# openSX70_ALADDIN_V381_20180125.net
KiCad netlist of a schematic drawn in EAGLE
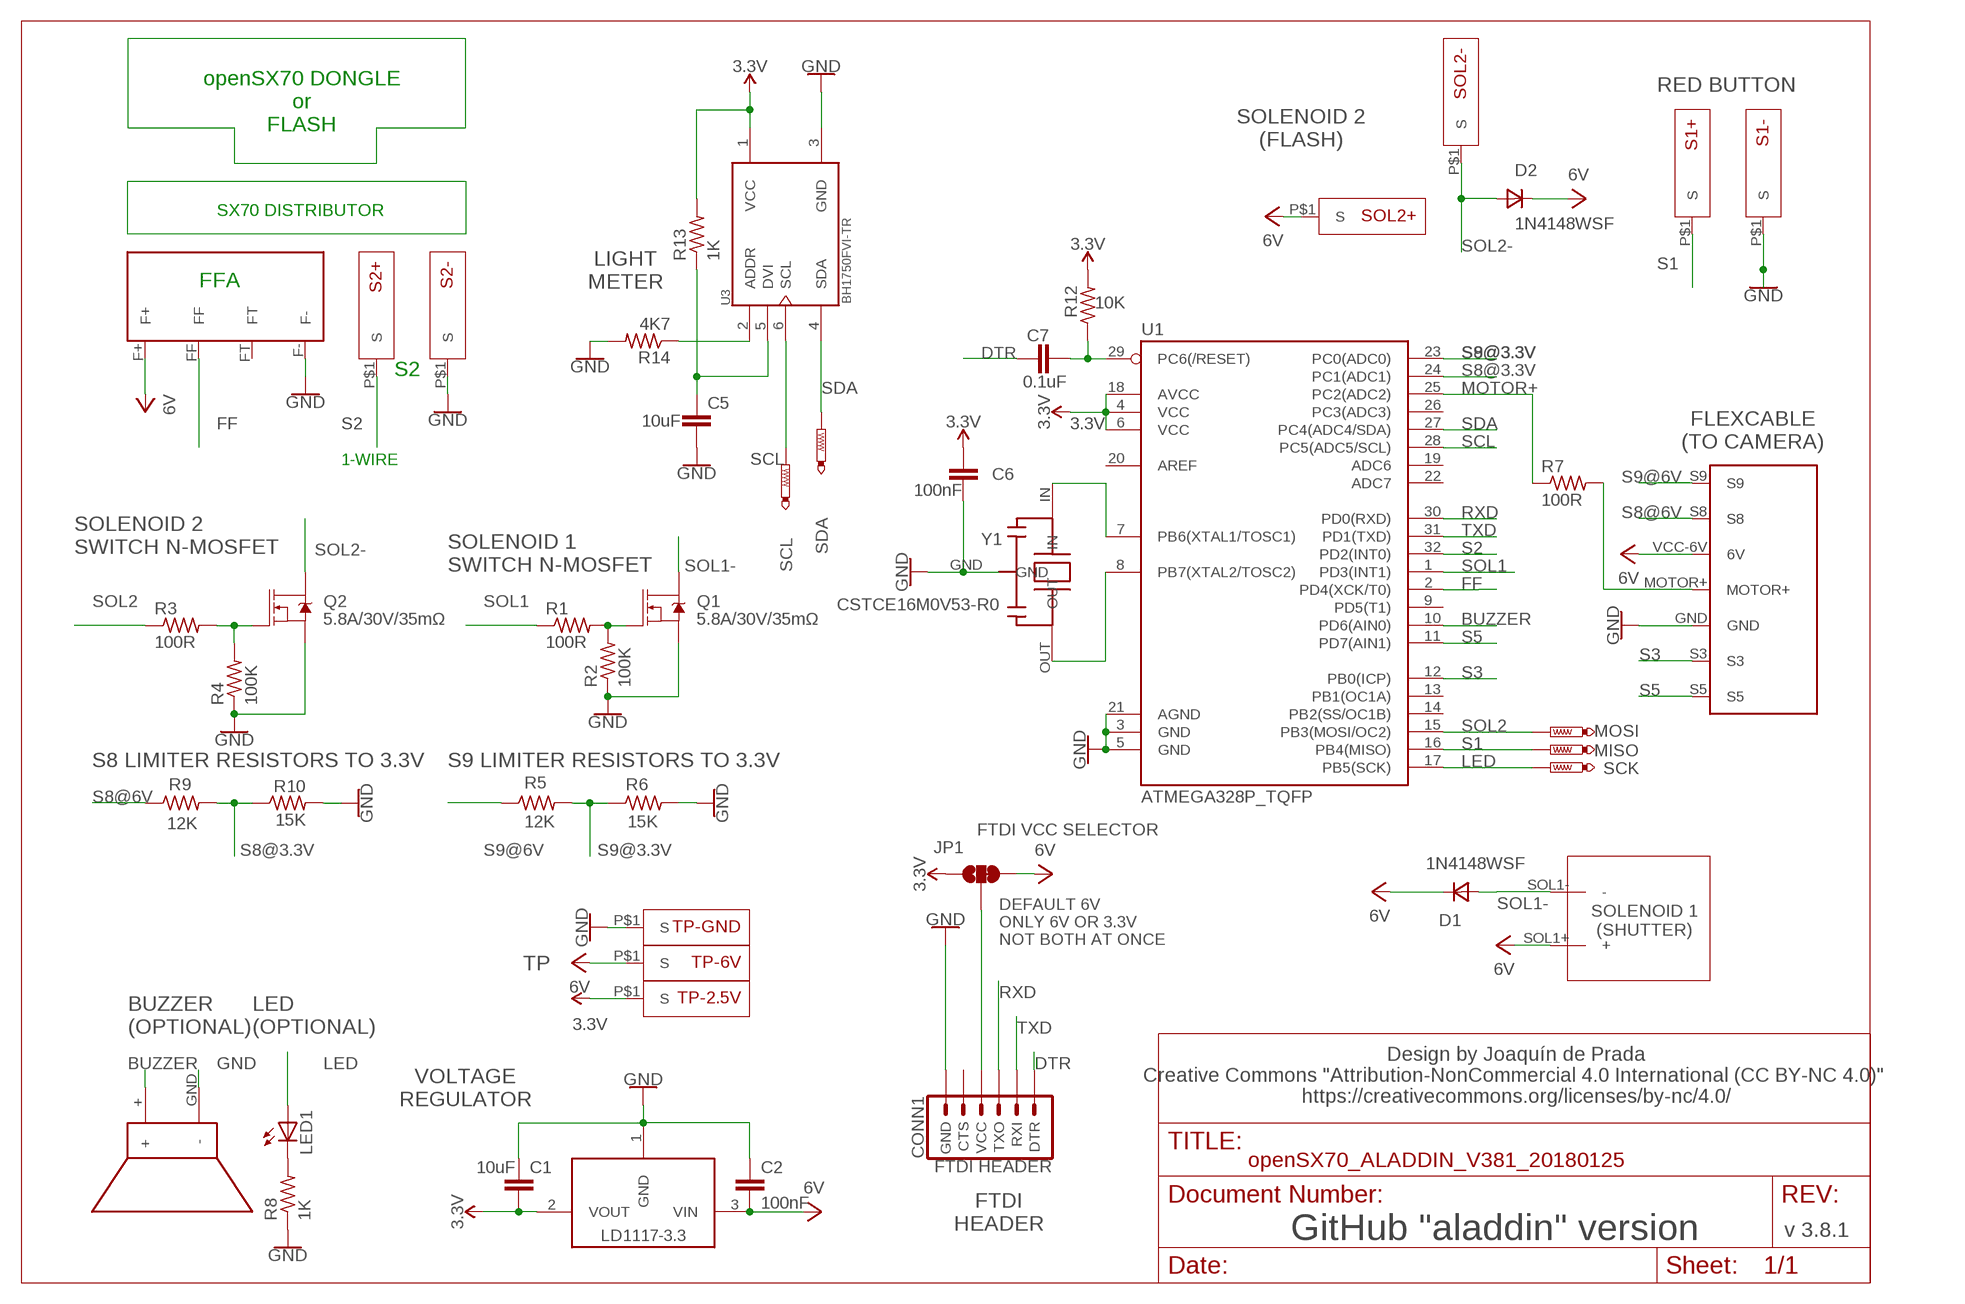
[diagram p0: schematic, sheet 1]

(export (version "E")
  (design (tool "Eeschema 10.0.6"))
  (components
    (comp (ref "BUZZ1")
      (value "CSET8-5G")
      (footprint "eagle-import:CSET8-5G_PACKAGE")
      (libsource (lib "eagle-import") (part "CSET8-5G"))
    )
    (comp (ref "C1")
      (value "10uF")
      (footprint "eagle-import:0603")
      (libsource (lib "eagle-import") (part "10UF-0603-6.3V-20%"))
    )
    (comp (ref "C2")
      (value "100nF")
      (footprint "eagle-import:C0603K")
      (libsource (lib "eagle-import") (part "C-EUC0603K"))
    )
    (comp (ref "C5")
      (value "10uF")
      (footprint "eagle-import:0603")
      (libsource (lib "eagle-import") (part "10UF-0603-6.3V-20%"))
    )
    (comp (ref "C6")
      (value "100nF")
      (footprint "eagle-import:C0603")
      (libsource (lib "eagle-import") (part "C-EUC0603"))
    )
    (comp (ref "C7")
      (value "0.1uF")
      (footprint "eagle-import:0603")
      (libsource (lib "eagle-import") (part "0.1UF-0603-25V-(+80/-20%)"))
    )
    (comp (ref "CONN1")
      (value "FTDI HEADER")
      (footprint "eagle-import:1X06")
      (libsource (lib "eagle-import") (part "6_PIN_SERIAL_TARGET"))
    )
    (comp (ref "D1")
      (value "1N4148WSF")
      (footprint "eagle-import:SOD323")
      (fields (field (name "MPN") "CDSOD323-T05C"))
      (libsource (lib "eagle-import") (part "DSOD323"))
    )
    (comp (ref "D2")
      (value "1N4148WSF")
      (footprint "eagle-import:SOD323")
      (fields (field (name "MPN") "CDSOD323-T05C"))
      (libsource (lib "eagle-import") (part "DSOD323"))
    )
    (comp (ref "JP1")
      (value "FTDI VCC SELECTOR")
      (footprint "eagle-import:SMT-JUMPER_3_1-NC_TRACE_SILK")
      (libsource (lib "eagle-import") (part "JUMPER-SMT_3_1-NC_TRACE_SILK"))
    )
    (comp (ref "LD11172.5V")
      (value "LD1117 3.3V")
      (footprint "eagle-import:SOT223")
      (fields (field (name "MF") "Advanced Monolithic Systems") (field (name "MP") "AMS1117-5.0"))
      (libsource (lib "eagle-import") (part "LD1117-3.3"))
    )
    (comp (ref "LED1")
      (value "LEDCHIPLED_0805")
      (footprint "eagle-import:CHIPLED_0805")
      (libsource (lib "eagle-import") (part "LEDCHIPLED_0805"))
    )
    (comp (ref "MISO")
      (value "PTR1TP08R")
      (footprint "eagle-import:TP08R")
      (libsource (lib "eagle-import") (part "PTR1TP08R"))
    )
    (comp (ref "MOSI")
      (value "PTR1TP08R")
      (footprint "eagle-import:TP08R")
      (libsource (lib "eagle-import") (part "PTR1TP08R"))
    )
    (comp (ref "Q1")
      (value "5.8A/30V/35mΩ")
      (footprint "eagle-import:SOT23-3")
      (libsource (lib "eagle-import") (part "MOSFET-NCH-AO3404A"))
    )
    (comp (ref "Q2")
      (value "5.8A/30V/35mΩ")
      (footprint "eagle-import:SOT23-3")
      (libsource (lib "eagle-import") (part "MOSFET-NCH-AO3404A"))
    )
    (comp (ref "R1")
      (value "100R")
      (footprint "eagle-import:R0603")
      (libsource (lib "eagle-import") (part "R-US_R0603"))
    )
    (comp (ref "R2")
      (value "100K")
      (footprint "eagle-import:R0603")
      (libsource (lib "eagle-import") (part "R-US_R0603"))
    )
    (comp (ref "R3")
      (value "100R")
      (footprint "eagle-import:R0603")
      (libsource (lib "eagle-import") (part "R-US_R0603"))
    )
    (comp (ref "R4")
      (value "100K")
      (footprint "eagle-import:R0603")
      (libsource (lib "eagle-import") (part "R-US_R0603"))
    )
    (comp (ref "R5")
      (value "12K")
      (footprint "eagle-import:R0603")
      (libsource (lib "eagle-import") (part "R-US_R0603"))
    )
    (comp (ref "R6")
      (value "15K")
      (footprint "eagle-import:R0603")
      (libsource (lib "eagle-import") (part "R-US_R0603"))
    )
    (comp (ref "R7")
      (value "100R")
      (footprint "eagle-import:R0603")
      (libsource (lib "eagle-import") (part "R-US_R0603"))
    )
    (comp (ref "R8")
      (value "1K")
      (footprint "eagle-import:R0603")
      (libsource (lib "eagle-import") (part "R-US_R0603"))
    )
    (comp (ref "R9")
      (value "12K")
      (footprint "eagle-import:R0603")
      (libsource (lib "eagle-import") (part "R-US_R0603"))
    )
    (comp (ref "R10")
      (value "15K")
      (footprint "eagle-import:R0603")
      (libsource (lib "eagle-import") (part "R-US_R0603"))
    )
    (comp (ref "R12")
      (value "10K")
      (footprint "eagle-import:R0603")
      (libsource (lib "eagle-import") (part "R-US_R0603"))
    )
    (comp (ref "R13")
      (value "1K")
      (footprint "eagle-import:R0603")
      (libsource (lib "eagle-import") (part "R-US_R0603"))
    )
    (comp (ref "R14")
      (value "4K7")
      (footprint "eagle-import:R0603")
      (libsource (lib "eagle-import") (part "R-US_R0603"))
    )
    (comp (ref "S1+")
      (value "SX70-S-PAD-NEW")
      (footprint "eagle-import:SX70-S-PAD2")
      (libsource (lib "eagle-import") (part "SX70-S-PAD-NEW"))
    )
    (comp (ref "S1-")
      (value "SX70-S-PAD-NEW")
      (footprint "eagle-import:SX70-S-PAD2")
      (libsource (lib "eagle-import") (part "SX70-S-PAD-NEW"))
    )
    (comp (ref "S2+")
      (value "SX70-S-PAD-NEW")
      (footprint "eagle-import:SX70-S-PAD2")
      (libsource (lib "eagle-import") (part "SX70-S-PAD-NEW"))
    )
    (comp (ref "S2-")
      (value "SX70-S-PAD-NEW")
      (footprint "eagle-import:SX70-S-PAD2")
      (libsource (lib "eagle-import") (part "SX70-S-PAD-NEW"))
    )
    (comp (ref "SCK")
      (value "PTR1TP08R")
      (footprint "eagle-import:TP08R")
      (libsource (lib "eagle-import") (part "PTR1TP08R"))
    )
    (comp (ref "SCL")
      (value "PTR1TP08R")
      (footprint "eagle-import:TP08R")
      (libsource (lib "eagle-import") (part "PTR1TP08R"))
    )
    (comp (ref "SDA")
      (value "PTR1TP08R")
      (footprint "eagle-import:TP08R")
      (libsource (lib "eagle-import") (part "PTR1TP08R"))
    )
    (comp (ref "SOL1")
      (value "SX70-SOLENOID1-2PADS")
      (footprint "eagle-import:SX70-SOLENOID1-2")
      (libsource (lib "eagle-import") (part "SX70-SOLENOID1-2PADS"))
    )
    (comp (ref "SOL2+")
      (value "SX70-S-PAD-NEW")
      (footprint "eagle-import:SX70-S-PAD2")
      (libsource (lib "eagle-import") (part "SX70-S-PAD-NEW"))
    )
    (comp (ref "SOL2-")
      (value "SX70-S-PAD-NEW")
      (footprint "eagle-import:SX70-S-PAD2")
      (libsource (lib "eagle-import") (part "SX70-S-PAD-NEW"))
    )
    (comp (ref "TP-2.5V")
      (value "SX70-S-PAD-NEW")
      (footprint "eagle-import:SX70-S-PAD2")
      (libsource (lib "eagle-import") (part "SX70-S-PAD-NEW"))
    )
    (comp (ref "TP-6V")
      (value "SX70-S-PAD-NEW")
      (footprint "eagle-import:SX70-S-PAD2")
      (libsource (lib "eagle-import") (part "SX70-S-PAD-NEW"))
    )
    (comp (ref "TP-GND")
      (value "SX70-S-PAD-NEW")
      (footprint "eagle-import:SX70-S-PAD2")
      (libsource (lib "eagle-import") (part "SX70-S-PAD-NEW"))
    )
    (comp (ref "U$1")
      (value "SX70-7-PAD")
      (footprint "eagle-import:SX70-7-PAD")
      (libsource (lib "eagle-import") (part "SX70-7-PAD"))
    )
    (comp (ref "U$2")
      (value "FFA")
      (footprint "eagle-import:FFA-PAD-PACKAGE")
      (libsource (lib "eagle-import") (part "SX70-FFA-PAD"))
    )
    (comp (ref "U1")
      (value "ATMEGA328P_TQFP")
      (footprint "eagle-import:TQFP32-08")
      (libsource (lib "eagle-import") (part "ATMEGA328P_TQFP"))
    )
    (comp (ref "U3")
      (value "BH1750FVI-TR")
      (footprint "eagle-import:SOTFL50P300X75-6N")
      (fields (field (name "MF") "Rohm"))
      (libsource (lib "eagle-import") (part "BH1750FVI-TR"))
    )
    (comp (ref "Y1")
      (value "CSTCE16M0V53-R0")
      (footprint "eagle-import:CFP95P160X100-3N")
      (fields (field (name "MF") "Murata"))
      (libsource (lib "eagle-import") (part "CSTCE16M0V53-R0"))
    )
  )
  (nets
    (net (code "1") (name "/BUZZER") (class "Default")
      (node (ref "BUZZ1") (pin "+") (pinfunction "+_+") (pintype "bidirectional"))
      (node (ref "U1") (pin "10") (pinfunction "PD6(AIN0)_10") (pintype "bidirectional"))
    )
    (net (code "2") (name "/DTR") (class "Default")
      (node (ref "C7") (pin "1") (pinfunction "1_1") (pintype "passive"))
      (node (ref "CONN1") (pin "1") (pinfunction "DTR_1") (pintype "passive"))
    )
    (net (code "3") (name "/FF") (class "Default")
      (node (ref "U$2") (pin "FF") (pinfunction "FF_FF") (pintype "bidirectional"))
      (node (ref "U1") (pin "2") (pinfunction "PD4(XCK/T0)_2") (pintype "bidirectional"))
    )
    (net (code "4") (name "/LED") (class "Default")
      (node (ref "LED1") (pin "A") (pinfunction "A_A") (pintype "passive"))
      (node (ref "SCK") (pin "TP") (pinfunction "TP_TP") (pintype "input"))
      (node (ref "U1") (pin "17") (pinfunction "PB5(SCK)_17") (pintype "bidirectional"))
    )
    (net (code "5") (name "/MOTOR+") (class "Default")
      (node (ref "R7") (pin "1") (pinfunction "1_1") (pintype "passive"))
      (node (ref "U1") (pin "25") (pinfunction "PC2(ADC2)_25") (pintype "bidirectional"))
    )
    (net (code "6") (name "/RXD") (class "Default")
      (node (ref "CONN1") (pin "3") (pinfunction "TXO_3") (pintype "passive"))
      (node (ref "U1") (pin "30") (pinfunction "PD0(RXD)_30") (pintype "bidirectional"))
    )
    (net (code "7") (name "/S1") (class "Default")
      (node (ref "MISO") (pin "TP") (pinfunction "TP_TP") (pintype "input"))
      (node (ref "S1+") (pin "P$1") (pinfunction "S_P$1") (pintype "bidirectional"))
      (node (ref "U1") (pin "16") (pinfunction "PB4(MISO)_16") (pintype "bidirectional"))
    )
    (net (code "8") (name "/S2") (class "Default")
      (node (ref "S2+") (pin "P$1") (pinfunction "S_P$1") (pintype "bidirectional"))
      (node (ref "U1") (pin "32") (pinfunction "PD2(INT0)_32") (pintype "bidirectional"))
    )
    (net (code "9") (name "/S3") (class "Default")
      (node (ref "U$1") (pin "S3") (pinfunction "S3_S3") (pintype "bidirectional"))
      (node (ref "U1") (pin "12") (pinfunction "PB0(ICP)_12") (pintype "bidirectional"))
    )
    (net (code "10") (name "/S5") (class "Default")
      (node (ref "U$1") (pin "S5") (pinfunction "S5_S5") (pintype "bidirectional"))
      (node (ref "U1") (pin "11") (pinfunction "PD7(AIN1)_11") (pintype "bidirectional"))
    )
    (net (code "11") (name "/S8@3.3V") (class "Default")
      (node (ref "R10") (pin "1") (pinfunction "1_1") (pintype "passive"))
      (node (ref "R9") (pin "2") (pinfunction "2_2") (pintype "passive"))
      (node (ref "U1") (pin "24") (pinfunction "PC1(ADC1)_24") (pintype "bidirectional"))
    )
    (net (code "12") (name "/S8@6V") (class "Default")
      (node (ref "R9") (pin "1") (pinfunction "1_1") (pintype "passive"))
      (node (ref "U$1") (pin "S8") (pinfunction "S8_S8") (pintype "bidirectional"))
    )
    (net (code "13") (name "/S9@3.3V") (class "Default")
      (node (ref "R5") (pin "2") (pinfunction "2_2") (pintype "passive"))
      (node (ref "R6") (pin "1") (pinfunction "1_1") (pintype "passive"))
      (node (ref "U1") (pin "23") (pinfunction "PC0(ADC0)_23") (pintype "bidirectional"))
    )
    (net (code "14") (name "/S9@6V") (class "Default")
      (node (ref "R5") (pin "1") (pinfunction "1_1") (pintype "passive"))
      (node (ref "U$1") (pin "S9") (pinfunction "S9_S9") (pintype "bidirectional"))
    )
    (net (code "15") (name "/SCL") (class "Default")
      (node (ref "SCL") (pin "TP") (pinfunction "TP_TP") (pintype "input"))
      (node (ref "U1") (pin "28") (pinfunction "PC5(ADC5/SCL)_28") (pintype "bidirectional"))
      (node (ref "U3") (pin "6") (pinfunction "SCL_6") (pintype "input"))
    )
    (net (code "16") (name "/SDA") (class "Default")
      (node (ref "SDA") (pin "TP") (pinfunction "TP_TP") (pintype "input"))
      (node (ref "U1") (pin "27") (pinfunction "PC4(ADC4/SDA)_27") (pintype "bidirectional"))
      (node (ref "U3") (pin "4") (pinfunction "SDA_4") (pintype "bidirectional"))
    )
    (net (code "17") (name "/SOL1") (class "Default")
      (node (ref "R1") (pin "1") (pinfunction "1_1") (pintype "passive"))
      (node (ref "U1") (pin "1") (pinfunction "PD3(INT1)_1") (pintype "bidirectional"))
    )
    (net (code "18") (name "/SOL1-") (class "Default")
      (node (ref "D1") (pin "2") (pinfunction "A_2") (pintype "passive"))
      (node (ref "Q1") (pin "3") (pinfunction "D_3") (pintype "bidirectional"))
      (node (ref "SOL1") (pin "SOL1-") (pinfunction "-_SOL1-") (pintype "bidirectional"))
    )
    (net (code "19") (name "/SOL2") (class "Default")
      (node (ref "MOSI") (pin "TP") (pinfunction "TP_TP") (pintype "input"))
      (node (ref "R3") (pin "1") (pinfunction "1_1") (pintype "passive"))
      (node (ref "U1") (pin "15") (pinfunction "PB3(MOSI/OC2)_15") (pintype "bidirectional"))
    )
    (net (code "20") (name "/SOL2-") (class "Default")
      (node (ref "D2") (pin "2") (pinfunction "A_2") (pintype "passive"))
      (node (ref "Q2") (pin "3") (pinfunction "D_3") (pintype "bidirectional"))
      (node (ref "SOL2-") (pin "P$1") (pinfunction "S_P$1") (pintype "bidirectional"))
    )
    (net (code "21") (name "/TXD") (class "Default")
      (node (ref "CONN1") (pin "2") (pinfunction "RXI_2") (pintype "passive"))
      (node (ref "U1") (pin "31") (pinfunction "PD1(TXD)_31") (pintype "bidirectional"))
    )
    (net (code "22") (name "3.3V") (class "Default")
      (node (ref "C1") (pin "2") (pinfunction "2_2") (pintype "passive"))
      (node (ref "C6") (pin "1") (pinfunction "1_1") (pintype "passive"))
      (node (ref "JP1") (pin "1") (pinfunction "1_1") (pintype "passive"))
      (node (ref "LD11172.5V") (pin "2") (pinfunction "VOUT_2") (pintype "bidirectional"))
      (node (ref "R12") (pin "2") (pinfunction "2_2") (pintype "passive"))
      (node (ref "R13") (pin "2") (pinfunction "2_2") (pintype "passive"))
      (node (ref "TP-2.5V") (pin "P$1") (pinfunction "S_P$1") (pintype "bidirectional"))
      (node (ref "U1") (pin "18") (pinfunction "AVCC_18") (pintype "bidirectional"))
      (node (ref "U1") (pin "4") (pinfunction "VCC_4") (pintype "bidirectional"))
      (node (ref "U1") (pin "6") (pinfunction "VCC_6") (pintype "bidirectional"))
      (node (ref "U3") (pin "1") (pinfunction "VCC_1") (pintype "power_in"))
    )
    (net (code "23") (name "6V") (class "Default")
      (node (ref "C2") (pin "2") (pinfunction "2_2") (pintype "passive"))
      (node (ref "D1") (pin "1") (pinfunction "C_1") (pintype "passive"))
      (node (ref "D2") (pin "1") (pinfunction "C_1") (pintype "passive"))
      (node (ref "JP1") (pin "3") (pinfunction "3_3") (pintype "passive"))
      (node (ref "LD11172.5V") (pin "3") (pinfunction "VIN_3") (pintype "bidirectional"))
      (node (ref "SOL1") (pin "SOL1+") (pinfunction "+_SOL1+") (pintype "bidirectional"))
      (node (ref "SOL2+") (pin "P$1") (pinfunction "S_P$1") (pintype "bidirectional"))
      (node (ref "TP-6V") (pin "P$1") (pinfunction "S_P$1") (pintype "bidirectional"))
      (node (ref "U$1") (pin "VCC-6V") (pinfunction "6V_VCC-6V") (pintype "bidirectional"))
      (node (ref "U$2") (pin "F+") (pinfunction "F+_F+") (pintype "bidirectional"))
    )
    (net (code "24") (name "GND") (class "Default")
      (node (ref "BUZZ1") (pin "GND") (pinfunction "-_GND") (pintype "bidirectional"))
      (node (ref "C1") (pin "1") (pinfunction "1_1") (pintype "passive"))
      (node (ref "C2") (pin "1") (pinfunction "1_1") (pintype "passive"))
      (node (ref "C5") (pin "2") (pinfunction "2_2") (pintype "passive"))
      (node (ref "C6") (pin "2") (pinfunction "2_2") (pintype "passive"))
      (node (ref "CONN1") (pin "6") (pinfunction "GND_6") (pintype "passive"))
      (node (ref "LD11172.5V") (pin "1") (pinfunction "GND_1") (pintype "bidirectional"))
      (node (ref "Q1") (pin "2") (pinfunction "S_2") (pintype "bidirectional"))
      (node (ref "Q2") (pin "2") (pinfunction "S_2") (pintype "bidirectional"))
      (node (ref "R10") (pin "2") (pinfunction "2_2") (pintype "passive"))
      (node (ref "R14") (pin "2") (pinfunction "2_2") (pintype "passive"))
      (node (ref "R2") (pin "1") (pinfunction "1_1") (pintype "passive"))
      (node (ref "R4") (pin "1") (pinfunction "1_1") (pintype "passive"))
      (node (ref "R6") (pin "2") (pinfunction "2_2") (pintype "passive"))
      (node (ref "R8") (pin "1") (pinfunction "1_1") (pintype "passive"))
      (node (ref "S1-") (pin "P$1") (pinfunction "S_P$1") (pintype "bidirectional"))
      (node (ref "S2-") (pin "P$1") (pinfunction "S_P$1") (pintype "bidirectional"))
      (node (ref "TP-GND") (pin "P$1") (pinfunction "S_P$1") (pintype "bidirectional"))
      (node (ref "U$1") (pin "GND") (pinfunction "GND_GND") (pintype "bidirectional"))
      (node (ref "U$2") (pin "F-") (pinfunction "F-_F-") (pintype "bidirectional"))
      (node (ref "U1") (pin "21") (pinfunction "AGND_21") (pintype "bidirectional"))
      (node (ref "U1") (pin "3") (pinfunction "GND_3") (pintype "bidirectional"))
      (node (ref "U1") (pin "5") (pinfunction "GND_5") (pintype "bidirectional"))
      (node (ref "U3") (pin "3") (pinfunction "GND_3") (pintype "power_in"))
      (node (ref "Y1") (pin "GND") (pinfunction "GND_GND") (pintype "passive"))
    )
    (net (code "25") (name "Net-(CONN1-VCC)") (class "Default")
      (node (ref "CONN1") (pin "4") (pinfunction "VCC_4") (pintype "passive"))
      (node (ref "JP1") (pin "2") (pinfunction "2_2") (pintype "passive"))
    )
    (net (code "26") (name "Net-(LED1-PadC)") (class "Default")
      (node (ref "LED1") (pin "C") (pinfunction "C_C") (pintype "passive"))
      (node (ref "R8") (pin "2") (pinfunction "2_2") (pintype "passive"))
    )
    (net (code "27") (name "Net-(Q1-G)") (class "Default")
      (node (ref "Q1") (pin "1") (pinfunction "G_1") (pintype "bidirectional"))
      (node (ref "R1") (pin "2") (pinfunction "2_2") (pintype "passive"))
      (node (ref "R2") (pin "2") (pinfunction "2_2") (pintype "passive"))
    )
    (net (code "28") (name "Net-(Q2-G)") (class "Default")
      (node (ref "Q2") (pin "1") (pinfunction "G_1") (pintype "bidirectional"))
      (node (ref "R3") (pin "2") (pinfunction "2_2") (pintype "passive"))
      (node (ref "R4") (pin "2") (pinfunction "2_2") (pintype "passive"))
    )
    (net (code "29") (name "Net-(R7-Pad2)") (class "Default")
      (node (ref "R7") (pin "2") (pinfunction "2_2") (pintype "passive"))
      (node (ref "U$1") (pin "MOTOR+") (pinfunction "MOTOR+_MOTOR+") (pintype "bidirectional"))
    )
    (net (code "30") (name "Net-(U1-PB6(XTAL1{slash}TOSC1))") (class "Default")
      (node (ref "U1") (pin "7") (pinfunction "PB6(XTAL1/TOSC1)_7") (pintype "bidirectional"))
      (node (ref "Y1") (pin "IN") (pinfunction "IN_IN") (pintype "input"))
    )
    (net (code "31") (name "Net-(U1-PB7(XTAL2{slash}TOSC2))") (class "Default")
      (node (ref "U1") (pin "8") (pinfunction "PB7(XTAL2/TOSC2)_8") (pintype "bidirectional"))
      (node (ref "Y1") (pin "OUT") (pinfunction "OUT_OUT") (pintype "output"))
    )
    (net (code "32") (name "Net-(U1-PC6({slash}RESET))") (class "Default")
      (node (ref "C7") (pin "2") (pinfunction "2_2") (pintype "passive"))
      (node (ref "R12") (pin "1") (pinfunction "1_1") (pintype "passive"))
      (node (ref "U1") (pin "29") (pinfunction "PC6(/RESET)_29") (pintype "bidirectional"))
    )
    (net (code "33") (name "Net-(U3-ADDR)") (class "Default")
      (node (ref "R14") (pin "1") (pinfunction "1_1") (pintype "passive"))
      (node (ref "U3") (pin "2") (pinfunction "ADDR_2") (pintype "input"))
    )
    (net (code "34") (name "Net-(U3-DVI)") (class "Default")
      (node (ref "C5") (pin "1") (pinfunction "1_1") (pintype "passive"))
      (node (ref "R13") (pin "1") (pinfunction "1_1") (pintype "passive"))
      (node (ref "U3") (pin "5") (pinfunction "DVI_5") (pintype "input"))
    )
    (net (code "35") (name "unconnected-(CONN1-CTS-Pad5)") (class "Default")
      (node (ref "CONN1") (pin "5") (pinfunction "CTS_5") (pintype "passive"))
    )
    (net (code "36") (name "unconnected-(U$2-PadFT)") (class "Default")
      (node (ref "U$2") (pin "FT") (pinfunction "FT_FT") (pintype "bidirectional"))
    )
    (net (code "37") (name "unconnected-(U1-ADC6-Pad19)") (class "Default")
      (node (ref "U1") (pin "19") (pinfunction "ADC6_19") (pintype "bidirectional"))
    )
    (net (code "38") (name "unconnected-(U1-ADC7-Pad22)") (class "Default")
      (node (ref "U1") (pin "22") (pinfunction "ADC7_22") (pintype "bidirectional"))
    )
    (net (code "39") (name "unconnected-(U1-AREF-Pad20)") (class "Default")
      (node (ref "U1") (pin "20") (pinfunction "AREF_20") (pintype "bidirectional"))
    )
    (net (code "40") (name "unconnected-(U1-PB1(OC1A)-Pad13)") (class "Default")
      (node (ref "U1") (pin "13") (pinfunction "PB1(OC1A)_13") (pintype "bidirectional"))
    )
    (net (code "41") (name "unconnected-(U1-PB2(SS{slash}OC1B)-Pad14)") (class "Default")
      (node (ref "U1") (pin "14") (pinfunction "PB2(SS/OC1B)_14") (pintype "bidirectional"))
    )
    (net (code "42") (name "unconnected-(U1-PC3(ADC3)-Pad26)") (class "Default")
      (node (ref "U1") (pin "26") (pinfunction "PC3(ADC3)_26") (pintype "bidirectional"))
    )
    (net (code "43") (name "unconnected-(U1-PD5(T1)-Pad9)") (class "Default")
      (node (ref "U1") (pin "9") (pinfunction "PD5(T1)_9") (pintype "bidirectional"))
    )
  )
)
